# Lin_Final_Project.net
KiCad netlist of a schematic drawn in EAGLE
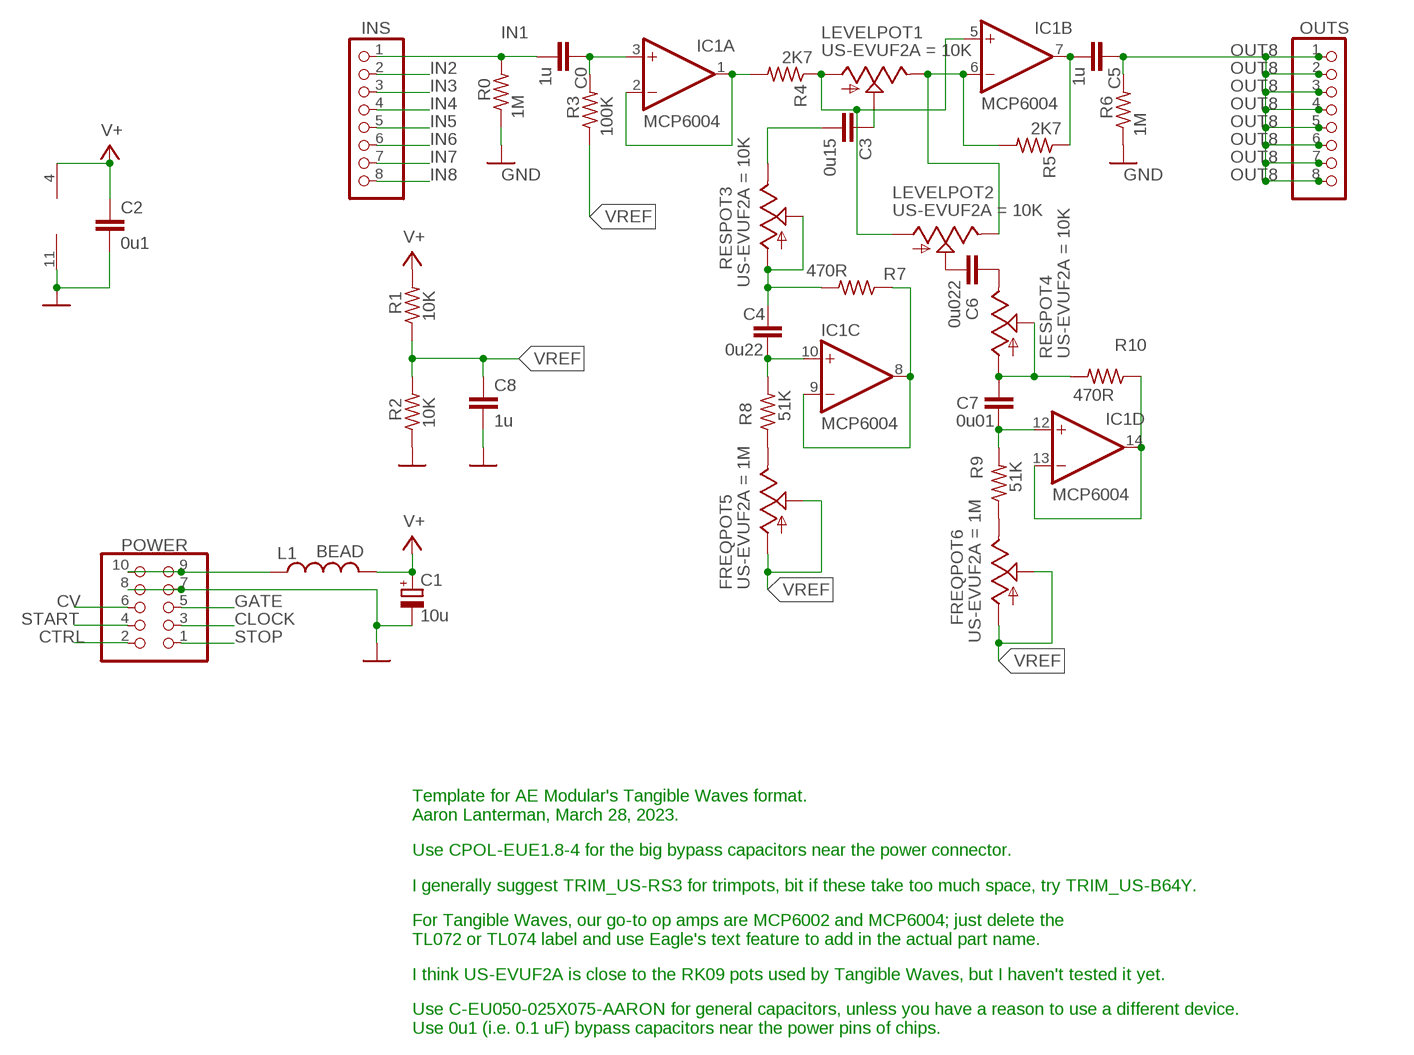
[diagram p0: schematic, sheet 1]

(export (version "E")
  (design (tool "Eeschema 10.0.6"))
  (components
    (comp (ref "C0")
      (value "1u")
      (footprint "eagle-import:C050-025X075-AARON")
      (libsource (lib "eagle-import") (part "C-EU050-025X075-AARON"))
    )
    (comp (ref "C1")
      (value "10u")
      (footprint "eagle-import:E1,8-4")
      (libsource (lib "eagle-import") (part "CPOL-EUE1.8-4"))
    )
    (comp (ref "C2")
      (value "0u1")
      (footprint "eagle-import:C050-025X075-AARON")
      (libsource (lib "eagle-import") (part "C-EU050-025X075-AARON"))
    )
    (comp (ref "C3")
      (value "0u15")
      (footprint "eagle-import:C050-025X075-AARON")
      (libsource (lib "eagle-import") (part "C-EU050-025X075-AARON"))
    )
    (comp (ref "C4")
      (value "0u22")
      (footprint "eagle-import:C050-025X075-AARON")
      (libsource (lib "eagle-import") (part "C-EU050-025X075-AARON"))
    )
    (comp (ref "C5")
      (value "1u")
      (footprint "eagle-import:C050-025X075-AARON")
      (libsource (lib "eagle-import") (part "C-EU050-025X075-AARON"))
    )
    (comp (ref "C6")
      (value "0u022")
      (footprint "eagle-import:C050-025X075-AARON")
      (libsource (lib "eagle-import") (part "C-EU050-025X075-AARON"))
    )
    (comp (ref "C7")
      (value "0u01")
      (footprint "eagle-import:C050-025X075-AARON")
      (libsource (lib "eagle-import") (part "C-EU050-025X075-AARON"))
    )
    (comp (ref "C8")
      (value "1u")
      (footprint "eagle-import:C050-025X075-AARON")
      (libsource (lib "eagle-import") (part "C-EU050-025X075-AARON"))
    )
    (comp (ref "FREQPOT5")
      (value "US-EVUF2A")
      (footprint "eagle-import:EVUF")
      (fields (field (name "US-EVUF2A") "1M"))
      (libsource (lib "eagle-import") (part "US-EVUAF2"))
    )
    (comp (ref "FREQPOT6")
      (value "US-EVUF2A")
      (footprint "eagle-import:EVUF")
      (fields (field (name "US-EVUF2A") "1M"))
      (libsource (lib "eagle-import") (part "US-EVUAF2"))
    )
    (comp (ref "IC1")
      (value "TL074P")
      (footprint "eagle-import:DIL14")
      (libsource (lib "eagle-import") (part "TL074P"))
    )
    (comp (ref "INS")
      (value "PINHD-1X8")
      (footprint "eagle-import:1X08")
      (libsource (lib "eagle-import") (part "PINHD-1X8"))
    )
    (comp (ref "L1")
      (value "BEAD")
      (footprint "eagle-import:0207_10")
      (libsource (lib "eagle-import") (part "L-US0207/10"))
    )
    (comp (ref "LEVELPOT1")
      (value "US-EVUF2A")
      (footprint "eagle-import:EVUF")
      (fields (field (name "US-EVUF2A") "10K"))
      (libsource (lib "eagle-import") (part "US-EVUAF2"))
    )
    (comp (ref "LEVELPOT2")
      (value "US-EVUF2A")
      (footprint "eagle-import:EVUF")
      (fields (field (name "US-EVUF2A") "10K"))
      (libsource (lib "eagle-import") (part "US-EVUAF2"))
    )
    (comp (ref "OUTS")
      (value "PINHD-1X8")
      (footprint "eagle-import:1X08")
      (libsource (lib "eagle-import") (part "PINHD-1X8"))
    )
    (comp (ref "POWER")
      (value "PINHD-2X5")
      (footprint "eagle-import:2X05")
      (libsource (lib "eagle-import") (part "PINHD-2X5"))
    )
    (comp (ref "R0")
      (value "1M")
      (footprint "eagle-import:0207_10")
      (libsource (lib "eagle-import") (part "R-US_0207/10"))
    )
    (comp (ref "R1")
      (value "10K")
      (footprint "eagle-import:0207_10")
      (libsource (lib "eagle-import") (part "R-US_0207/10"))
    )
    (comp (ref "R2")
      (value "10K")
      (footprint "eagle-import:0207_10")
      (libsource (lib "eagle-import") (part "R-US_0207/10"))
    )
    (comp (ref "R3")
      (value "100K")
      (footprint "eagle-import:0207_10")
      (libsource (lib "eagle-import") (part "R-US_0207/10"))
    )
    (comp (ref "R4")
      (value "2K7")
      (footprint "eagle-import:0207_10")
      (libsource (lib "eagle-import") (part "R-US_0207/10"))
    )
    (comp (ref "R5")
      (value "2K7")
      (footprint "eagle-import:0207_10")
      (libsource (lib "eagle-import") (part "R-US_0207/10"))
    )
    (comp (ref "R6")
      (value "1M")
      (footprint "eagle-import:0207_10")
      (libsource (lib "eagle-import") (part "R-US_0207/10"))
    )
    (comp (ref "R7")
      (value "470R")
      (footprint "eagle-import:0207_10")
      (libsource (lib "eagle-import") (part "R-US_0207/10"))
    )
    (comp (ref "R8")
      (value "51K")
      (footprint "eagle-import:0207_10")
      (libsource (lib "eagle-import") (part "R-US_0207/10"))
    )
    (comp (ref "R9")
      (value "51K")
      (footprint "eagle-import:0207_10")
      (libsource (lib "eagle-import") (part "R-US_0207/10"))
    )
    (comp (ref "R10")
      (value "470R")
      (footprint "eagle-import:0207_10")
      (libsource (lib "eagle-import") (part "R-US_0207/10"))
    )
    (comp (ref "RESPOT3")
      (value "US-EVUF2A")
      (footprint "eagle-import:EVUF")
      (fields (field (name "US-EVUF2A") "10K"))
      (libsource (lib "eagle-import") (part "US-EVUAF2"))
    )
    (comp (ref "RESPOT4")
      (value "US-EVUF2A")
      (footprint "eagle-import:EVUF")
      (fields (field (name "US-EVUF2A") "10K"))
      (libsource (lib "eagle-import") (part "US-EVUAF2"))
    )
  )
  (nets
    (net (code "1") (name "/CLOCK") (class "Default")
      (node (ref "POWER") (pin "3") (pinfunction "3_3") (pintype "passive"))
    )
    (net (code "2") (name "/CTRL") (class "Default")
      (node (ref "POWER") (pin "2") (pinfunction "2_2") (pintype "passive"))
    )
    (net (code "3") (name "/CV") (class "Default")
      (node (ref "POWER") (pin "6") (pinfunction "6_6") (pintype "passive"))
    )
    (net (code "4") (name "/GATE") (class "Default")
      (node (ref "POWER") (pin "5") (pinfunction "5_5") (pintype "passive"))
    )
    (net (code "5") (name "/IN1") (class "Default")
      (node (ref "C0") (pin "2") (pinfunction "2_2") (pintype "passive"))
      (node (ref "INS") (pin "1") (pinfunction "1_1") (pintype "passive"))
      (node (ref "R0") (pin "2") (pinfunction "2_2") (pintype "passive"))
    )
    (net (code "6") (name "/IN2") (class "Default")
      (node (ref "INS") (pin "2") (pinfunction "2_2") (pintype "passive"))
    )
    (net (code "7") (name "/IN3") (class "Default")
      (node (ref "INS") (pin "3") (pinfunction "3_3") (pintype "passive"))
    )
    (net (code "8") (name "/IN4") (class "Default")
      (node (ref "INS") (pin "4") (pinfunction "4_4") (pintype "passive"))
    )
    (net (code "9") (name "/IN5") (class "Default")
      (node (ref "INS") (pin "5") (pinfunction "5_5") (pintype "passive"))
    )
    (net (code "10") (name "/IN6") (class "Default")
      (node (ref "INS") (pin "6") (pinfunction "6_6") (pintype "passive"))
    )
    (net (code "11") (name "/IN7") (class "Default")
      (node (ref "INS") (pin "7") (pinfunction "7_7") (pintype "passive"))
    )
    (net (code "12") (name "/IN8") (class "Default")
      (node (ref "INS") (pin "8") (pinfunction "8_8") (pintype "passive"))
    )
    (net (code "13") (name "/OUT8") (class "Default")
      (node (ref "C5") (pin "1") (pinfunction "1_1") (pintype "passive"))
      (node (ref "OUTS") (pin "1") (pinfunction "1_1") (pintype "passive"))
      (node (ref "OUTS") (pin "2") (pinfunction "2_2") (pintype "passive"))
      (node (ref "OUTS") (pin "3") (pinfunction "3_3") (pintype "passive"))
      (node (ref "OUTS") (pin "4") (pinfunction "4_4") (pintype "passive"))
      (node (ref "OUTS") (pin "5") (pinfunction "5_5") (pintype "passive"))
      (node (ref "OUTS") (pin "6") (pinfunction "6_6") (pintype "passive"))
      (node (ref "OUTS") (pin "7") (pinfunction "7_7") (pintype "passive"))
      (node (ref "OUTS") (pin "8") (pinfunction "8_8") (pintype "passive"))
      (node (ref "R6") (pin "2") (pinfunction "2_2") (pintype "passive"))
    )
    (net (code "14") (name "/START") (class "Default")
      (node (ref "POWER") (pin "4") (pinfunction "4_4") (pintype "passive"))
    )
    (net (code "15") (name "/STOP") (class "Default")
      (node (ref "POWER") (pin "1") (pinfunction "1_1") (pintype "passive"))
    )
    (net (code "16") (name "GND") (class "Default")
      (node (ref "C1") (pin "-") (pinfunction "-_-") (pintype "passive"))
      (node (ref "C2") (pin "2") (pinfunction "2_2") (pintype "passive"))
      (node (ref "C8") (pin "2") (pinfunction "2_2") (pintype "passive"))
      (node (ref "IC1") (pin "11") (pinfunction "V-_11") (pintype "power_in"))
      (node (ref "POWER") (pin "7") (pinfunction "7_7") (pintype "passive"))
      (node (ref "POWER") (pin "8") (pinfunction "8_8") (pintype "passive"))
      (node (ref "R0") (pin "1") (pinfunction "1_1") (pintype "passive"))
      (node (ref "R2") (pin "1") (pinfunction "1_1") (pintype "passive"))
      (node (ref "R6") (pin "1") (pinfunction "1_1") (pintype "passive"))
    )
    (net (code "17") (name "Net-(FREQPOT5-E)") (class "Default")
      (node (ref "FREQPOT5") (pin "3") (pinfunction "E_3") (pintype "passive"))
      (node (ref "R8") (pin "1") (pinfunction "1_1") (pintype "passive"))
    )
    (net (code "18") (name "Net-(FREQPOT6-E)") (class "Default")
      (node (ref "FREQPOT6") (pin "3") (pinfunction "E_3") (pintype "passive"))
      (node (ref "R9") (pin "1") (pinfunction "1_1") (pintype "passive"))
    )
    (net (code "19") (name "Net-(IC1A-+IN)") (class "Default")
      (node (ref "C0") (pin "1") (pinfunction "1_1") (pintype "passive"))
      (node (ref "IC1") (pin "3") (pinfunction "+IN_3") (pintype "input"))
      (node (ref "R3") (pin "2") (pinfunction "2_2") (pintype "passive"))
    )
    (net (code "20") (name "Net-(IC1A--IN)") (class "Default")
      (node (ref "IC1") (pin "1") (pinfunction "OUT_1") (pintype "output"))
      (node (ref "IC1") (pin "2") (pinfunction "-IN_2") (pintype "input"))
      (node (ref "R4") (pin "2") (pinfunction "2_2") (pintype "passive"))
    )
    (net (code "21") (name "Net-(IC1B-+IN)") (class "Default")
      (node (ref "IC1") (pin "5") (pinfunction "+IN_5") (pintype "input"))
      (node (ref "LEVELPOT1") (pin "1") (pinfunction "A_1") (pintype "passive"))
      (node (ref "LEVELPOT2") (pin "1") (pinfunction "A_1") (pintype "passive"))
      (node (ref "R4") (pin "1") (pinfunction "1_1") (pintype "passive"))
    )
    (net (code "22") (name "Net-(IC1B--IN)") (class "Default")
      (node (ref "IC1") (pin "6") (pinfunction "-IN_6") (pintype "input"))
      (node (ref "LEVELPOT1") (pin "3") (pinfunction "E_3") (pintype "passive"))
      (node (ref "LEVELPOT2") (pin "3") (pinfunction "E_3") (pintype "passive"))
      (node (ref "R5") (pin "2") (pinfunction "2_2") (pintype "passive"))
    )
    (net (code "23") (name "Net-(IC1B-OUT)") (class "Default")
      (node (ref "C5") (pin "2") (pinfunction "2_2") (pintype "passive"))
      (node (ref "IC1") (pin "7") (pinfunction "OUT_7") (pintype "output"))
      (node (ref "R5") (pin "1") (pinfunction "1_1") (pintype "passive"))
    )
    (net (code "24") (name "Net-(IC1C-+IN)") (class "Default")
      (node (ref "C4") (pin "2") (pinfunction "2_2") (pintype "passive"))
      (node (ref "IC1") (pin "10") (pinfunction "+IN_10") (pintype "input"))
      (node (ref "R8") (pin "2") (pinfunction "2_2") (pintype "passive"))
    )
    (net (code "25") (name "Net-(IC1C--IN)") (class "Default")
      (node (ref "IC1") (pin "8") (pinfunction "OUT_8") (pintype "output"))
      (node (ref "IC1") (pin "9") (pinfunction "-IN_9") (pintype "input"))
      (node (ref "R7") (pin "1") (pinfunction "1_1") (pintype "passive"))
    )
    (net (code "26") (name "Net-(IC1D-+IN)") (class "Default")
      (node (ref "C7") (pin "2") (pinfunction "2_2") (pintype "passive"))
      (node (ref "IC1") (pin "12") (pinfunction "+IN_12") (pintype "input"))
      (node (ref "R9") (pin "2") (pinfunction "2_2") (pintype "passive"))
    )
    (net (code "27") (name "Net-(IC1D--IN)") (class "Default")
      (node (ref "IC1") (pin "13") (pinfunction "-IN_13") (pintype "input"))
      (node (ref "IC1") (pin "14") (pinfunction "OUT_14") (pintype "output"))
      (node (ref "R10") (pin "1") (pinfunction "1_1") (pintype "passive"))
    )
    (net (code "28") (name "Net-(L1-Pad1)") (class "Default")
      (node (ref "L1") (pin "1") (pinfunction "1_1") (pintype "passive"))
      (node (ref "POWER") (pin "10") (pinfunction "10_10") (pintype "passive"))
      (node (ref "POWER") (pin "9") (pinfunction "9_9") (pintype "passive"))
    )
    (net (code "29") (name "Net-(LEVELPOT1-S)") (class "Default")
      (node (ref "C3") (pin "1") (pinfunction "1_1") (pintype "passive"))
      (node (ref "LEVELPOT1") (pin "2") (pinfunction "S_2") (pintype "passive"))
    )
    (net (code "30") (name "Net-(LEVELPOT2-S)") (class "Default")
      (node (ref "C6") (pin "2") (pinfunction "2_2") (pintype "passive"))
      (node (ref "LEVELPOT2") (pin "2") (pinfunction "S_2") (pintype "passive"))
    )
    (net (code "31") (name "Net-(RESPOT3-A)") (class "Default")
      (node (ref "C4") (pin "1") (pinfunction "1_1") (pintype "passive"))
      (node (ref "R7") (pin "2") (pinfunction "2_2") (pintype "passive"))
      (node (ref "RESPOT3") (pin "1") (pinfunction "A_1") (pintype "passive"))
      (node (ref "RESPOT3") (pin "2") (pinfunction "S_2") (pintype "passive"))
    )
    (net (code "32") (name "Net-(RESPOT3-E)") (class "Default")
      (node (ref "C3") (pin "2") (pinfunction "2_2") (pintype "passive"))
      (node (ref "RESPOT3") (pin "3") (pinfunction "E_3") (pintype "passive"))
    )
    (net (code "33") (name "Net-(RESPOT4-A)") (class "Default")
      (node (ref "C7") (pin "1") (pinfunction "1_1") (pintype "passive"))
      (node (ref "R10") (pin "2") (pinfunction "2_2") (pintype "passive"))
      (node (ref "RESPOT4") (pin "1") (pinfunction "A_1") (pintype "passive"))
      (node (ref "RESPOT4") (pin "2") (pinfunction "S_2") (pintype "passive"))
    )
    (net (code "34") (name "Net-(RESPOT4-E)") (class "Default")
      (node (ref "C6") (pin "1") (pinfunction "1_1") (pintype "passive"))
      (node (ref "RESPOT4") (pin "3") (pinfunction "E_3") (pintype "passive"))
    )
    (net (code "35") (name "V+") (class "Default")
      (node (ref "C1") (pin "+") (pinfunction "+_+") (pintype "passive"))
      (node (ref "C2") (pin "1") (pinfunction "1_1") (pintype "passive"))
      (node (ref "IC1") (pin "4") (pinfunction "V+_4") (pintype "power_in"))
      (node (ref "L1") (pin "2") (pinfunction "2_2") (pintype "passive"))
      (node (ref "R1") (pin "2") (pinfunction "2_2") (pintype "passive"))
    )
    (net (code "36") (name "VREF") (class "Default")
      (node (ref "C8") (pin "1") (pinfunction "1_1") (pintype "passive"))
      (node (ref "FREQPOT5") (pin "1") (pinfunction "A_1") (pintype "passive"))
      (node (ref "FREQPOT5") (pin "2") (pinfunction "S_2") (pintype "passive"))
      (node (ref "FREQPOT6") (pin "1") (pinfunction "A_1") (pintype "passive"))
      (node (ref "FREQPOT6") (pin "2") (pinfunction "S_2") (pintype "passive"))
      (node (ref "R1") (pin "1") (pinfunction "1_1") (pintype "passive"))
      (node (ref "R2") (pin "2") (pinfunction "2_2") (pintype "passive"))
      (node (ref "R3") (pin "1") (pinfunction "1_1") (pintype "passive"))
    )
  )
)
